# DCDC_12V.net
KiCad netlist of a schematic drawn in Altium Designer
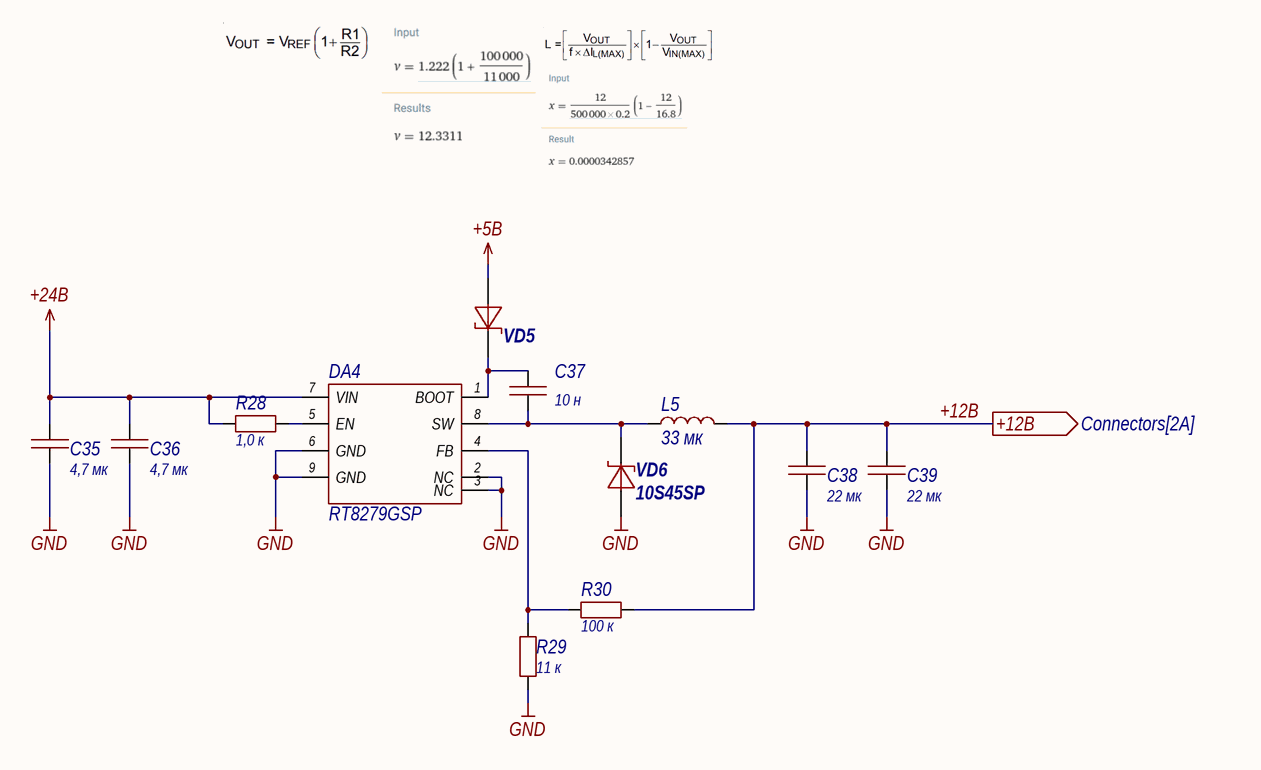
[diagram p0: DCDC_12V.SchDoc]

(export (version "E")
  (design (tool "Eeschema 10.0.6"))
  (components
    (comp (ref "C35")
      (value "4,7 мк")
      (footprint "1206C")
      (description "Конденсатор")
      (fields (field (name "PART NUMBER") "Capacitor_4,7u_10_50V_X7R_1206C") (field (name "TOLERANCE") "0,1"))
      (libsource (lib "Hydrolib") (part "Capacitor"))
    )
    (comp (ref "C36")
      (value "4,7 мк")
      (footprint "1206C")
      (description "Конденсатор")
      (fields (field (name "PART NUMBER") "Capacitor_4,7u_10_50V_X7R_1206C") (field (name "TOLERANCE") "0,1"))
      (libsource (lib "Hydrolib") (part "Capacitor"))
    )
    (comp (ref "C37")
      (value "10 н")
      (footprint "0603C")
      (description "Конденсатор")
      (fields (field (name "PART NUMBER") "Capacitor_10n_10_50V_X7R_0603C") (field (name "TOLERANCE") "0,1"))
      (libsource (lib "Hydrolib") (part "Capacitor"))
    )
    (comp (ref "C38")
      (value "22 мк")
      (footprint "1210C")
      (description "Конденсатор")
      (fields (field (name "PART NUMBER") "Capacitor_22u_10_25V_X7R_1210C") (field (name "TOLERANCE") "0,1"))
      (libsource (lib "Hydrolib") (part "Capacitor"))
    )
    (comp (ref "C39")
      (value "22 мк")
      (footprint "1210C")
      (description "Конденсатор")
      (fields (field (name "PART NUMBER") "Capacitor_22u_10_25V_X7R_1210C") (field (name "TOLERANCE") "0,1"))
      (libsource (lib "Hydrolib") (part "Capacitor"))
    )
    (comp (ref "DA4")
      (value "RT8279GSP")
      (footprint "8SOP(Exposed_Pad)")
      (description "Преобразователь постоянного тока понижающий подстраиваемый выход 5А")
      (libsource (lib "Hydrolib") (part "RT8279GSP"))
    )
    (comp (ref "L5")
      (value "33 мк")
      (footprint "IHLP-4040")
      (description "ЧИП-индуктивность экранированная 33мкГн ±20% 4,4A 94,5мОм 4040")
      (fields (field (name "PART NUMBER") "IHLP4040DZER330M11"))
      (libsource (lib "Hydrolib") (part "Inductance"))
    )
    (comp (ref "R28")
      (value "1,0 к")
      (footprint "0603R")
      (description "Резистор номиналом 1,0 кОм и точностью 1%")
      (fields (field (name "PART NUMBER") "Resistor_1.0k_1_0603") (field (name "TOLERANCE") "1%"))
      (libsource (lib "Hydrolib") (part "Resistor"))
    )
    (comp (ref "R29")
      (value "11 к")
      (footprint "0603R")
      (description "Резистор номиналом 11 кОм и точностью 1%")
      (fields (field (name "PART NUMBER") "Resistor_11k_1_0603") (field (name "TOLERANCE") "1%"))
      (libsource (lib "") (part "Resistor_1"))
    )
    (comp (ref "R30")
      (value "100 к")
      (footprint "0603R")
      (description "Резистор номиналом 100 кОм и точностью 1%")
      (fields (field (name "PART NUMBER") "Resistor_100k_1_0603") (field (name "TOLERANCE") "1%"))
      (libsource (lib "") (part "Resistor_2"))
    )
    (comp (ref "VD5")
      (value "BAT54WS")
      (footprint "SOD-323")
      (description "Диод шоттки на 30 В, ном. ток 0.2 А")
      (libsource (lib "Hydrolib") (part "Schottky_diode"))
    )
    (comp (ref "VD6")
      (value "10S45SP")
      (footprint "TO-277")
      (description "Диод шоттки на 45 В, ном. ток 10 А")
      (libsource (lib "Hydrolib") (part "Schottky_diode"))
    )
  )
  (nets
    (net (code "1") (name "+5В") (class "Default")
      (node (ref "VD5") (pin "1") (pinfunction "1_1") (pintype "passive"))
    )
    (net (code "2") (name "+24В") (class "Default")
      (node (ref "C35") (pin "2") (pinfunction "2_2") (pintype "passive"))
      (node (ref "C36") (pin "2") (pinfunction "2_2") (pintype "passive"))
      (node (ref "DA4") (pin "7") (pinfunction "VIN_7") (pintype "passive"))
      (node (ref "R28") (pin "2") (pinfunction "2_2") (pintype "passive"))
    )
    (net (code "3") (name "/+12В") (class "Default")
      (node (ref "C38") (pin "2") (pinfunction "2_2") (pintype "passive"))
      (node (ref "C39") (pin "2") (pinfunction "2_2") (pintype "passive"))
      (node (ref "L5") (pin "2") (pinfunction "2_2") (pintype "passive"))
      (node (ref "R30") (pin "2") (pinfunction "2_2") (pintype "passive"))
    )
    (net (code "4") (name "GND") (class "Default")
      (node (ref "C35") (pin "1") (pinfunction "1_1") (pintype "passive"))
      (node (ref "C36") (pin "1") (pinfunction "1_1") (pintype "passive"))
      (node (ref "C38") (pin "1") (pinfunction "1_1") (pintype "passive"))
      (node (ref "C39") (pin "1") (pinfunction "1_1") (pintype "passive"))
      (node (ref "DA4") (pin "2") (pinfunction "NC_2") (pintype "passive"))
      (node (ref "DA4") (pin "3") (pinfunction "NC_3") (pintype "passive"))
      (node (ref "DA4") (pin "6") (pinfunction "GND_6") (pintype "passive"))
      (node (ref "DA4") (pin "9") (pinfunction "GND_9") (pintype "passive"))
      (node (ref "R29") (pin "1") (pinfunction "1_1") (pintype "passive"))
      (node (ref "VD6") (pin "1") (pinfunction "1_1") (pintype "passive"))
    )
    (net (code "5") (name "Net-(DA4-BOOT)") (class "Default")
      (node (ref "C37") (pin "2") (pinfunction "2_2") (pintype "passive"))
      (node (ref "DA4") (pin "1") (pinfunction "BOOT_1") (pintype "passive"))
      (node (ref "VD5") (pin "2") (pinfunction "2_2") (pintype "passive"))
    )
    (net (code "6") (name "Net-(DA4-EN)") (class "Default")
      (node (ref "DA4") (pin "5") (pinfunction "EN_5") (pintype "passive"))
      (node (ref "R28") (pin "1") (pinfunction "1_1") (pintype "passive"))
    )
    (net (code "7") (name "Net-(DA4-FB)") (class "Default")
      (node (ref "DA4") (pin "4") (pinfunction "FB_4") (pintype "passive"))
      (node (ref "R29") (pin "2") (pinfunction "2_2") (pintype "passive"))
      (node (ref "R30") (pin "1") (pinfunction "1_1") (pintype "passive"))
    )
    (net (code "8") (name "Net-(DA4-SW)") (class "Default")
      (node (ref "C37") (pin "1") (pinfunction "1_1") (pintype "passive"))
      (node (ref "DA4") (pin "8") (pinfunction "SW_8") (pintype "passive"))
      (node (ref "L5") (pin "1") (pinfunction "1_1") (pintype "passive"))
      (node (ref "VD6") (pin "2") (pinfunction "2_2") (pintype "passive"))
    )
  )
)
